# OIS_Anakart.net
KiCad netlist of a schematic drawn in Altium Designer
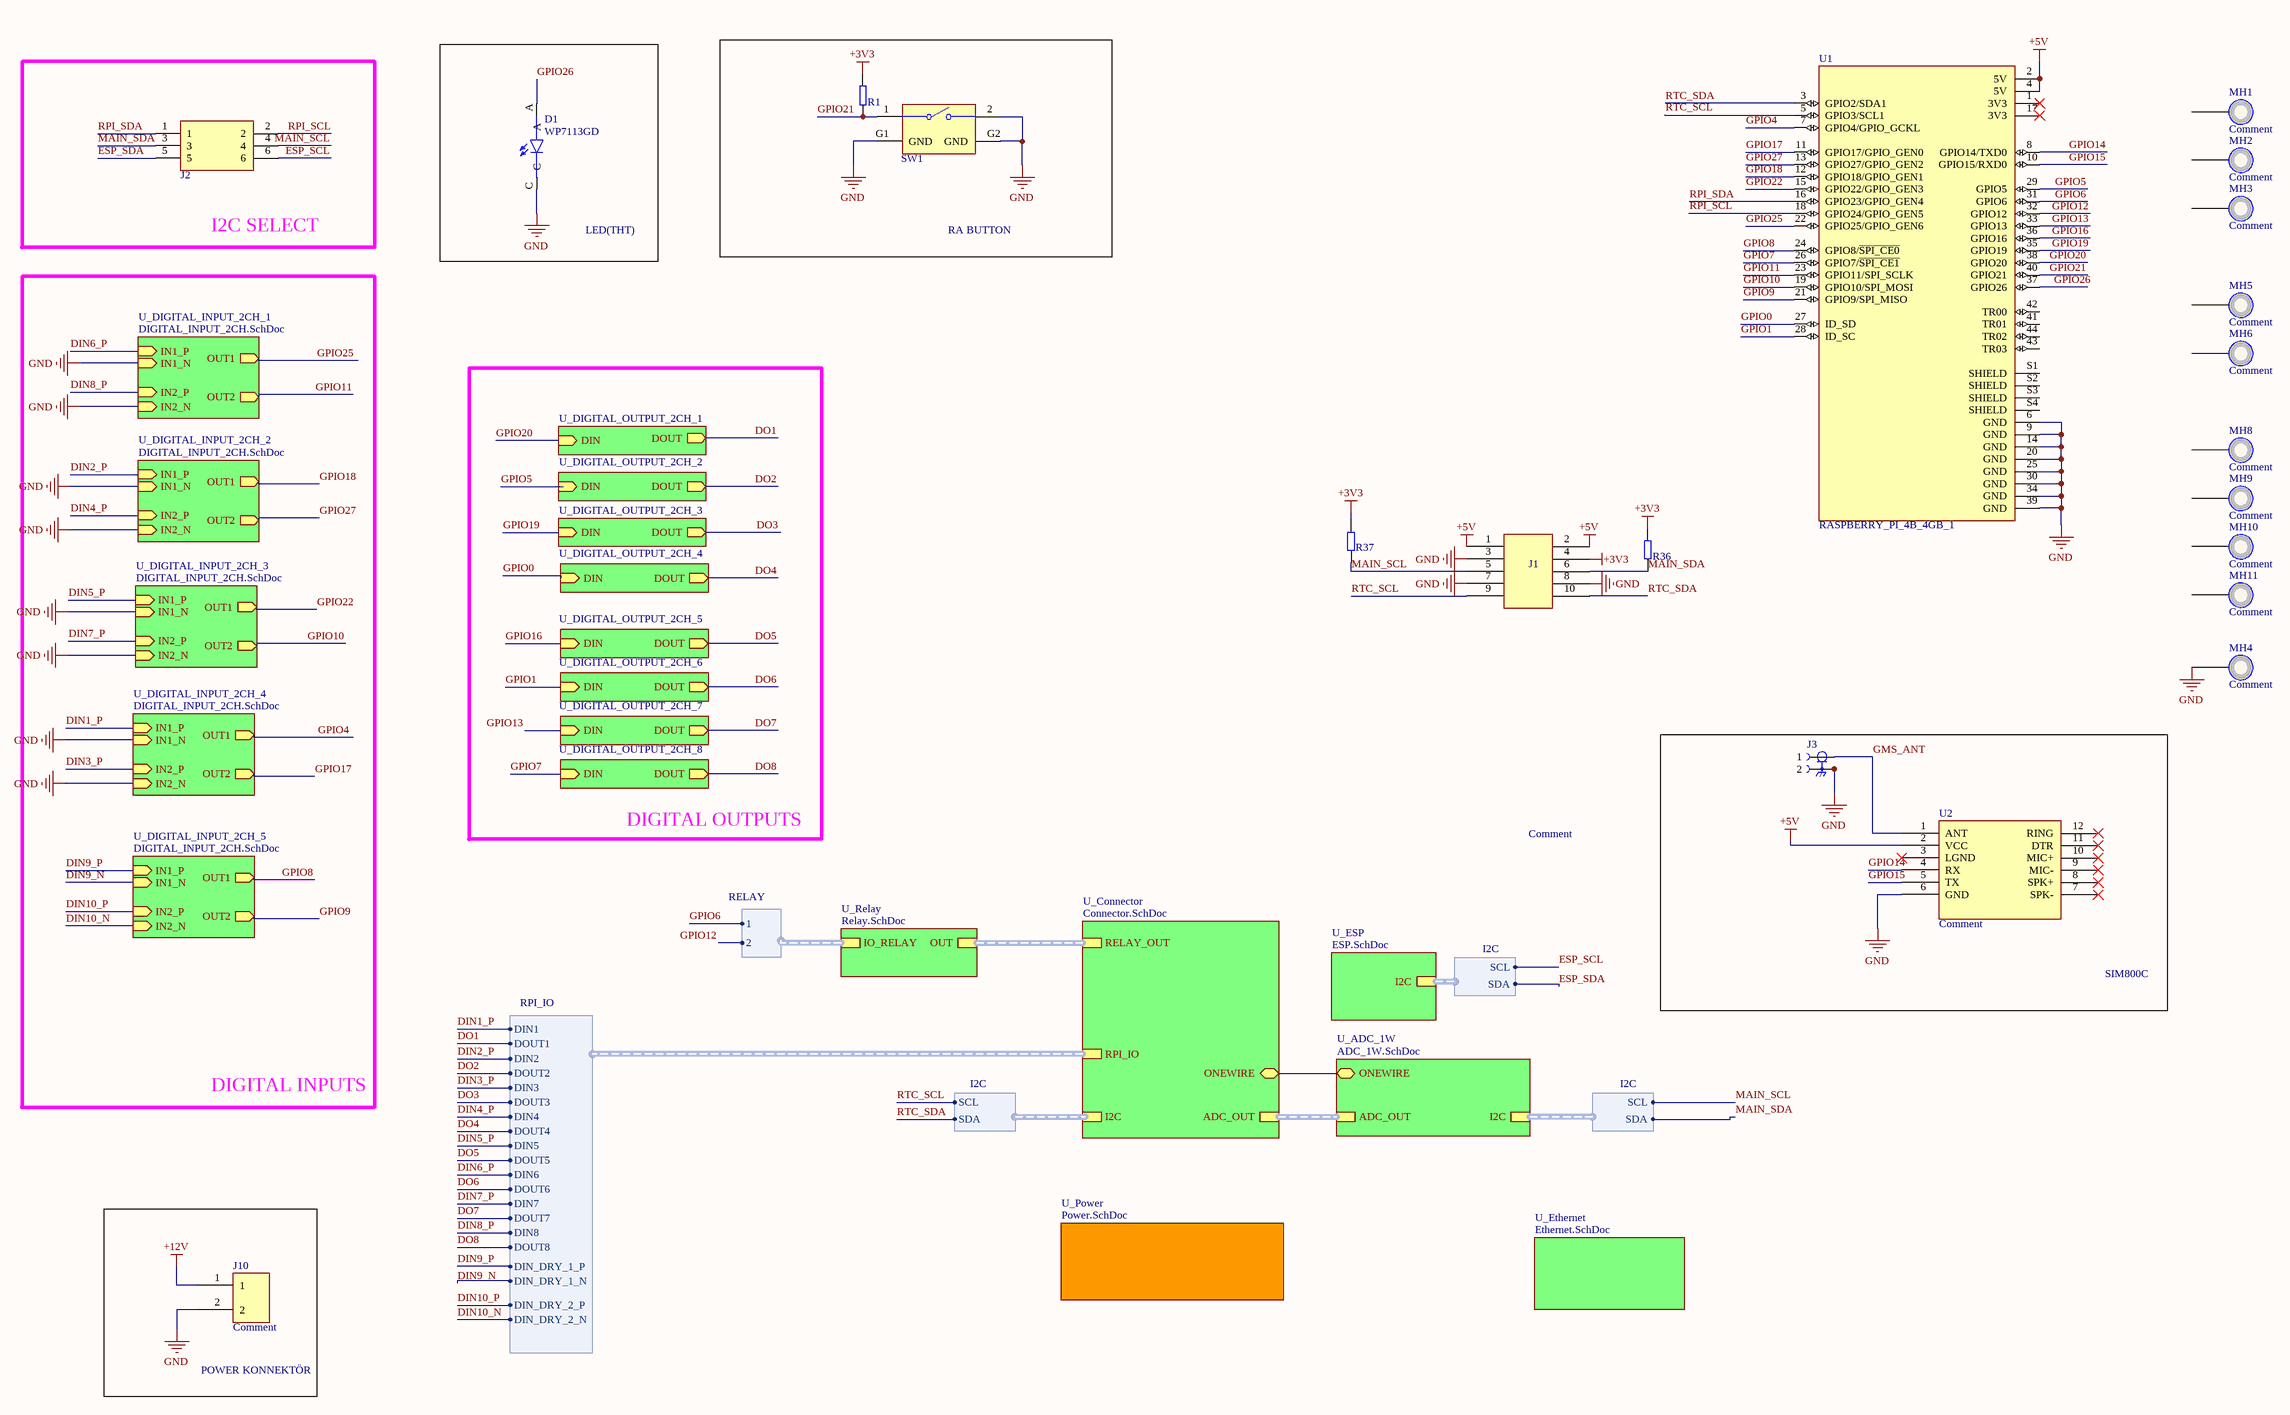
[diagram p0: OIS_Anakart.SchDoc]

(export (version "E")
  (design (tool "Eeschema 10.0.6"))
  (components
    (comp (ref "D1")
      (value "WP7113GD")
      (footprint "LED_WP7113GD")
      (description "Green 568nm LED Indication THT")
      (fields (field (name "MF") "Kingbright"))
      (libsource (lib "anayurt") (part "WP7113GD"))
    )
    (comp (ref "J1")
      (value "Comment")
      (footprint "2.54_5x2P")
      (description "CONN10P_5x2P")
      (libsource (lib "anayurt") (part "CONN10P_5x2P"))
    )
    (comp (ref "J2")
      (value "GRPB032VWQS-RC")
      (footprint "CONN_6P_1.27MM")
      (description "CONN HEADER SMD 6POS 1.27MM")
      (fields (field (name "MANUFACTURER") "Sullins Connector Solutions"))
      (libsource (lib "anayurt") (part "CONN_6P_2R"))
    )
    (comp (ref "J3")
      (value "RF2-49B-T-00-50-G-HDW")
      (footprint "ADAMTECH_RF2-49B-T-00-50-G-HDW")
      (description "RF SMA CONNECTOR")
      (fields (field (name "MF") "Adam Tech") (field (name "PART NUMBER") "2057-RF2-49B-T-00-50-G-HDW-ND"))
      (libsource (lib "anayurt") (part "RF2-49B-T-00-50-G-HDW"))
    )
    (comp (ref "J10")
      (value "Comment")
      (footprint "691213510002")
      (description "5.08 mm _ 2 pins")
      (fields (field (name "PART NUMBER") "2P_508"))
      (libsource (lib "anayurt") (part "CONN_2P"))
    )
    (comp (ref "MH1")
      (value "Comment")
      (footprint "m3_3.2x6")
      (fields (field (name "PART NUMBER") "M3_Vida") (field (name "CREATED BY") "Recep Aydin"))
      (libsource (lib "anayurt") (part "MountingHole"))
    )
    (comp (ref "MH2")
      (value "Comment")
      (footprint "m3_3.2x6")
      (fields (field (name "PART NUMBER") "M3_Vida") (field (name "CREATED BY") "Recep Aydin"))
      (libsource (lib "anayurt") (part "MountingHole"))
    )
    (comp (ref "MH3")
      (value "Comment")
      (footprint "m3_3.2x6")
      (fields (field (name "PART NUMBER") "M3_Vida") (field (name "CREATED BY") "Recep Aydin"))
      (libsource (lib "anayurt") (part "MountingHole"))
    )
    (comp (ref "MH4")
      (value "Comment")
      (footprint "m3_3.2x6")
      (fields (field (name "PART NUMBER") "M3_Vida") (field (name "CREATED BY") "Recep Aydin"))
      (libsource (lib "anayurt") (part "MountingHole"))
    )
    (comp (ref "MH5")
      (value "Comment")
      (footprint "m3_3.2x6")
      (fields (field (name "PART NUMBER") "M3_Vida") (field (name "CREATED BY") "Recep Aydin"))
      (libsource (lib "anayurt") (part "MountingHole"))
    )
    (comp (ref "MH6")
      (value "Comment")
      (footprint "m3_3.2x6")
      (fields (field (name "PART NUMBER") "M3_Vida") (field (name "CREATED BY") "Recep Aydin"))
      (libsource (lib "anayurt") (part "MountingHole"))
    )
    (comp (ref "MH8")
      (value "Comment")
      (footprint "m3_3.2x6")
      (fields (field (name "PART NUMBER") "M3_Vida") (field (name "CREATED BY") "Recep Aydin"))
      (libsource (lib "anayurt") (part "MountingHole"))
    )
    (comp (ref "MH9")
      (value "Comment")
      (footprint "m3_3.2x6")
      (fields (field (name "PART NUMBER") "M3_Vida") (field (name "CREATED BY") "Recep Aydin"))
      (libsource (lib "anayurt") (part "MountingHole"))
    )
    (comp (ref "MH10")
      (value "Comment")
      (footprint "m3_3.2x6")
      (fields (field (name "PART NUMBER") "M3_Vida") (field (name "CREATED BY") "Recep Aydin"))
      (libsource (lib "anayurt") (part "MountingHole"))
    )
    (comp (ref "MH11")
      (value "Comment")
      (footprint "m3_3.2x6")
      (fields (field (name "PART NUMBER") "M3_Vida") (field (name "CREATED BY") "Recep Aydin"))
      (libsource (lib "anayurt") (part "MountingHole"))
    )
    (comp (ref "R1")
      (value "1K")
      (footprint "R0402")
      (description "RES SMD 1K OHM 0.1% 1/16W 0402")
      (fields (field (name "PART NUMBER") "RT0402BRE071KL") (field (name "TOLERANCE") "0.1%"))
      (libsource (lib "anayurt") (part "RES"))
    )
    (comp (ref "R36")
      (value "1K")
      (footprint "R0402")
      (description "RES SMD 1K OHM 0.1% 1/16W 0402")
      (fields (field (name "PART NUMBER") "RT0402BRE071KL") (field (name "TOLERANCE") "0.1%"))
      (libsource (lib "anayurt") (part "RES"))
    )
    (comp (ref "R37")
      (value "1K")
      (footprint "R0402")
      (description "RES SMD 1K OHM 0.1% 1/16W 0402")
      (fields (field (name "PART NUMBER") "RT0402BRE071KL") (field (name "TOLERANCE") "0.1%"))
      (libsource (lib "anayurt") (part "RES"))
    )
    (comp (ref "SW1")
      (value "431256083716")
      (footprint "4312560837x6")
      (description "THT Tact Switch 6x6 mm Right Angled")
      (fields (field (name "MANUFACTURER") "Wurth Elektronik"))
      (libsource (lib "anayurt") (part "431256083716"))
    )
    (comp (ref "U1")
      (value "RASPBERRY_PI_4B_4GB_1")
      (footprint "MODULE_RASPBERRY_PI_4B_4GB_2")
      (description "MODULE_RASPBERRY_PI_4B_4GB")
      (fields (field (name "MF") "Raspberry Pi") (field (name "MP") "RASPBERRY PI 4B/4GB"))
      (libsource (lib "anayurt") (part "RASPBERRY_PI_4B_4GB_1"))
    )
    (comp (ref "U2")
      (value "Comment")
      (footprint "SIM800C_EVAL")
      (fields (field (name "PART NUMBER") "SIM800C_EVAL"))
      (libsource (lib "anayurt") (part "SIM800C_EVAL"))
    )
  )
  (nets
    (net (code "4") (name "+3V3") (class "Default")
      (node (ref "J1") (pin "4") (pinfunction "4_4") (pintype "passive"))
      (node (ref "R1") (pin "1") (pinfunction "1_1") (pintype "passive"))
      (node (ref "R36") (pin "1") (pinfunction "1_1") (pintype "passive"))
      (node (ref "R37") (pin "1") (pinfunction "1_1") (pintype "passive"))
    )
    (net (code "5") (name "+5V") (class "Default")
      (node (ref "J1") (pin "1") (pinfunction "1_1") (pintype "passive"))
      (node (ref "J1") (pin "2") (pinfunction "2_2") (pintype "passive"))
      (node (ref "U1") (pin "2") (pinfunction "5V_2") (pintype "power_in"))
      (node (ref "U1") (pin "4") (pinfunction "5V_4") (pintype "power_in"))
      (node (ref "U2") (pin "2") (pinfunction "VCC_2") (pintype "passive"))
    )
    (net (code "6") (name "+12V") (class "Default")
      (node (ref "J10") (pin "1") (pinfunction "1_1") (pintype "passive"))
    )
    (net (code "31") (name "/ESP_SCL") (class "Default")
      (node (ref "J2") (pin "6") (pinfunction "6_6") (pintype "passive"))
    )
    (net (code "32") (name "/ESP_SDA") (class "Default")
      (node (ref "J2") (pin "5") (pinfunction "5_5") (pintype "passive"))
    )
    (net (code "33") (name "/GMS_ANT") (class "Default")
      (node (ref "J3") (pin "1") (pinfunction "1_1") (pintype "passive"))
      (node (ref "U2") (pin "1") (pinfunction "ANT_1") (pintype "passive"))
    )
    (net (code "34") (name "/GPIO0") (class "Default")
      (node (ref "U1") (pin "27") (pinfunction "ID_SD_27") (pintype "bidirectional"))
    )
    (net (code "35") (name "/GPIO1") (class "Default")
      (node (ref "U1") (pin "28") (pinfunction "ID_SC_28") (pintype "bidirectional"))
    )
    (net (code "36") (name "/GPIO4") (class "Default")
      (node (ref "U1") (pin "7") (pinfunction "GPIO4/GPIO_GCKL_7") (pintype "bidirectional"))
    )
    (net (code "37") (name "/GPIO5") (class "Default")
      (node (ref "U1") (pin "29") (pinfunction "GPIO5_29") (pintype "bidirectional"))
    )
    (net (code "38") (name "/GPIO6") (class "Default")
      (node (ref "U1") (pin "31") (pinfunction "GPIO6_31") (pintype "bidirectional"))
    )
    (net (code "39") (name "/GPIO7") (class "Default")
      (node (ref "U1") (pin "26") (pinfunction "GPIO7/~{SPI_CE1}_26") (pintype "bidirectional"))
    )
    (net (code "40") (name "/GPIO8") (class "Default")
      (node (ref "U1") (pin "24") (pinfunction "GPIO8/~{SPI_CE0}_24") (pintype "bidirectional"))
    )
    (net (code "41") (name "/GPIO9") (class "Default")
      (node (ref "U1") (pin "21") (pinfunction "GPIO9/SPI_MISO_21") (pintype "bidirectional"))
    )
    (net (code "42") (name "/GPIO10") (class "Default")
      (node (ref "U1") (pin "19") (pinfunction "GPIO10/SPI_MOSI_19") (pintype "bidirectional"))
    )
    (net (code "43") (name "/GPIO11") (class "Default")
      (node (ref "U1") (pin "23") (pinfunction "GPIO11/SPI_SCLK_23") (pintype "bidirectional"))
    )
    (net (code "44") (name "/GPIO12") (class "Default")
      (node (ref "U1") (pin "32") (pinfunction "GPIO12_32") (pintype "bidirectional"))
    )
    (net (code "45") (name "/GPIO13") (class "Default")
      (node (ref "U1") (pin "33") (pinfunction "GPIO13_33") (pintype "bidirectional"))
    )
    (net (code "46") (name "/GPIO14") (class "Default")
      (node (ref "U1") (pin "8") (pinfunction "GPIO14/TXD0_8") (pintype "bidirectional"))
      (node (ref "U2") (pin "4") (pinfunction "RX_4") (pintype "passive"))
    )
    (net (code "47") (name "/GPIO15") (class "Default")
      (node (ref "U1") (pin "10") (pinfunction "GPIO15/RXD0_10") (pintype "bidirectional"))
      (node (ref "U2") (pin "5") (pinfunction "TX_5") (pintype "passive"))
    )
    (net (code "48") (name "/GPIO16") (class "Default")
      (node (ref "U1") (pin "36") (pinfunction "GPIO16_36") (pintype "bidirectional"))
    )
    (net (code "49") (name "/GPIO17") (class "Default")
      (node (ref "U1") (pin "11") (pinfunction "GPIO17/GPIO_GEN0_11") (pintype "bidirectional"))
    )
    (net (code "50") (name "/GPIO18") (class "Default")
      (node (ref "U1") (pin "12") (pinfunction "GPIO18/GPIO_GEN1_12") (pintype "bidirectional"))
    )
    (net (code "51") (name "/GPIO19") (class "Default")
      (node (ref "U1") (pin "35") (pinfunction "GPIO19_35") (pintype "bidirectional"))
    )
    (net (code "52") (name "/GPIO20") (class "Default")
      (node (ref "U1") (pin "38") (pinfunction "GPIO20_38") (pintype "bidirectional"))
    )
    (net (code "53") (name "/GPIO21") (class "Default")
      (node (ref "R1") (pin "2") (pinfunction "2_2") (pintype "passive"))
      (node (ref "SW1") (pin "1") (pinfunction "1_1") (pintype "passive"))
      (node (ref "U1") (pin "40") (pinfunction "GPIO21_40") (pintype "bidirectional"))
    )
    (net (code "54") (name "/GPIO22") (class "Default")
      (node (ref "U1") (pin "15") (pinfunction "GPIO22/GPIO_GEN3_15") (pintype "bidirectional"))
    )
    (net (code "55") (name "/GPIO25") (class "Default")
      (node (ref "U1") (pin "22") (pinfunction "GPIO25/GPIO_GEN6_22") (pintype "bidirectional"))
    )
    (net (code "56") (name "/GPIO26") (class "Default")
      (node (ref "D1") (pin "A") (pinfunction "A_A") (pintype "passive"))
      (node (ref "U1") (pin "37") (pinfunction "GPIO26_37") (pintype "bidirectional"))
    )
    (net (code "57") (name "/GPIO27") (class "Default")
      (node (ref "U1") (pin "13") (pinfunction "GPIO27/GPIO_GEN2_13") (pintype "bidirectional"))
    )
    (net (code "67") (name "/MAIN_SCL") (class "Default")
      (node (ref "J1") (pin "5") (pinfunction "5_5") (pintype "passive"))
      (node (ref "J2") (pin "4") (pinfunction "4_4") (pintype "passive"))
      (node (ref "R37") (pin "2") (pinfunction "2_2") (pintype "passive"))
    )
    (net (code "68") (name "/MAIN_SDA") (class "Default")
      (node (ref "J1") (pin "6") (pinfunction "6_6") (pintype "passive"))
      (node (ref "J2") (pin "3") (pinfunction "3_3") (pintype "passive"))
      (node (ref "R36") (pin "2") (pinfunction "2_2") (pintype "passive"))
    )
    (net (code "73") (name "/RPI_SCL") (class "Default")
      (node (ref "J2") (pin "2") (pinfunction "2_2") (pintype "passive"))
      (node (ref "U1") (pin "18") (pinfunction "GPIO24/GPIO_GEN5_18") (pintype "bidirectional"))
    )
    (net (code "74") (name "/RPI_SDA") (class "Default")
      (node (ref "J2") (pin "1") (pinfunction "1_1") (pintype "passive"))
      (node (ref "U1") (pin "16") (pinfunction "GPIO23/GPIO_GEN4_16") (pintype "bidirectional"))
    )
    (net (code "75") (name "/RTC_SCL") (class "Default")
      (node (ref "J1") (pin "9") (pinfunction "9_9") (pintype "passive"))
      (node (ref "U1") (pin "5") (pinfunction "GPIO3/SCL1_5") (pintype "bidirectional"))
    )
    (net (code "76") (name "/RTC_SDA") (class "Default")
      (node (ref "J1") (pin "10") (pinfunction "10_10") (pintype "passive"))
      (node (ref "U1") (pin "3") (pinfunction "GPIO2/SDA1_3") (pintype "bidirectional"))
    )
    (net (code "80") (name "GND") (class "Default")
      (node (ref "D1") (pin "C") (pinfunction "C_C") (pintype "passive"))
      (node (ref "J1") (pin "3") (pinfunction "3_3") (pintype "passive"))
      (node (ref "J1") (pin "7") (pinfunction "7_7") (pintype "passive"))
      (node (ref "J1") (pin "8") (pinfunction "8_8") (pintype "passive"))
      (node (ref "J10") (pin "2") (pinfunction "2_2") (pintype "passive"))
      (node (ref "J3") (pin "SH1") (pinfunction "2_SH1") (pintype "passive"))
      (node (ref "J3") (pin "SH2") (pinfunction "2_SH2") (pintype "passive"))
      (node (ref "J3") (pin "SH3") (pinfunction "2_SH3") (pintype "passive"))
      (node (ref "J3") (pin "SH4") (pinfunction "2_SH4") (pintype "passive"))
      (node (ref "MH4") (pin "1") (pinfunction "1_1") (pintype "passive"))
      (node (ref "SW1") (pin "2") (pinfunction "2_2") (pintype "passive"))
      (node (ref "SW1") (pin "G1") (pinfunction "GND_G1") (pintype "passive"))
      (node (ref "SW1") (pin "G2") (pinfunction "GND_G2") (pintype "passive"))
      (node (ref "U1") (pin "14") (pinfunction "GND_14") (pintype "power_in"))
      (node (ref "U1") (pin "20") (pinfunction "GND_20") (pintype "power_in"))
      (node (ref "U1") (pin "25") (pinfunction "GND_25") (pintype "power_in"))
      (node (ref "U1") (pin "30") (pinfunction "GND_30") (pintype "power_in"))
      (node (ref "U1") (pin "34") (pinfunction "GND_34") (pintype "power_in"))
      (node (ref "U1") (pin "39") (pinfunction "GND_39") (pintype "power_in"))
      (node (ref "U1") (pin "6") (pinfunction "GND_6") (pintype "power_in"))
      (node (ref "U1") (pin "9") (pinfunction "GND_9") (pintype "power_in"))
      (node (ref "U2") (pin "6") (pinfunction "GND_6") (pintype "passive"))
    )
    (net (code "81") (name "unconnected-(MH1-Pad1)") (class "Default")
      (node (ref "MH1") (pin "1") (pinfunction "1_1") (pintype "passive"))
    )
    (net (code "82") (name "unconnected-(MH2-Pad1)") (class "Default")
      (node (ref "MH2") (pin "1") (pinfunction "1_1") (pintype "passive"))
    )
    (net (code "83") (name "unconnected-(MH3-Pad1)") (class "Default")
      (node (ref "MH3") (pin "1") (pinfunction "1_1") (pintype "passive"))
    )
    (net (code "84") (name "unconnected-(MH5-Pad1)") (class "Default")
      (node (ref "MH5") (pin "1") (pinfunction "1_1") (pintype "passive"))
    )
    (net (code "85") (name "unconnected-(MH6-Pad1)") (class "Default")
      (node (ref "MH6") (pin "1") (pinfunction "1_1") (pintype "passive"))
    )
    (net (code "86") (name "unconnected-(MH8-Pad1)") (class "Default")
      (node (ref "MH8") (pin "1") (pinfunction "1_1") (pintype "passive"))
    )
    (net (code "87") (name "unconnected-(MH9-Pad1)") (class "Default")
      (node (ref "MH9") (pin "1") (pinfunction "1_1") (pintype "passive"))
    )
    (net (code "88") (name "unconnected-(MH10-Pad1)") (class "Default")
      (node (ref "MH10") (pin "1") (pinfunction "1_1") (pintype "passive"))
    )
    (net (code "89") (name "unconnected-(MH11-Pad1)") (class "Default")
      (node (ref "MH11") (pin "1") (pinfunction "1_1") (pintype "passive"))
    )
    (net (code "90") (name "unconnected-(U1-3V3-Pad1)") (class "Default")
      (node (ref "U1") (pin "1") (pinfunction "3V3_1") (pintype "power_in+no_connect"))
    )
    (net (code "91") (name "unconnected-(U1-3V3-Pad17)") (class "Default")
      (node (ref "U1") (pin "17") (pinfunction "3V3_17") (pintype "power_in+no_connect"))
    )
    (net (code "92") (name "unconnected-(U1-SHIELD-PadS1)") (class "Default")
      (node (ref "U1") (pin "S1") (pinfunction "SHIELD_S1") (pintype "power_in"))
    )
    (net (code "93") (name "unconnected-(U1-SHIELD-PadS2)") (class "Default")
      (node (ref "U1") (pin "S2") (pinfunction "SHIELD_S2") (pintype "power_in"))
    )
    (net (code "94") (name "unconnected-(U1-SHIELD-PadS3)") (class "Default")
      (node (ref "U1") (pin "S3") (pinfunction "SHIELD_S3") (pintype "power_in"))
    )
    (net (code "95") (name "unconnected-(U1-SHIELD-PadS4)") (class "Default")
      (node (ref "U1") (pin "S4") (pinfunction "SHIELD_S4") (pintype "power_in"))
    )
    (net (code "96") (name "unconnected-(U1-TR00-Pad42)") (class "Default")
      (node (ref "U1") (pin "42") (pinfunction "TR00_42") (pintype "bidirectional"))
    )
    (net (code "97") (name "unconnected-(U1-TR01-Pad41)") (class "Default")
      (node (ref "U1") (pin "41") (pinfunction "TR01_41") (pintype "bidirectional"))
    )
    (net (code "98") (name "unconnected-(U1-TR02-Pad44)") (class "Default")
      (node (ref "U1") (pin "44") (pinfunction "TR02_44") (pintype "bidirectional"))
    )
    (net (code "99") (name "unconnected-(U1-TR03-Pad43)") (class "Default")
      (node (ref "U1") (pin "43") (pinfunction "TR03_43") (pintype "bidirectional"))
    )
    (net (code "100") (name "unconnected-(U2-DTR-Pad11)") (class "Default")
      (node (ref "U2") (pin "11") (pinfunction "DTR_11") (pintype "passive+no_connect"))
    )
    (net (code "101") (name "unconnected-(U2-LGND-Pad3)") (class "Default")
      (node (ref "U2") (pin "3") (pinfunction "LGND_3") (pintype "passive+no_connect"))
    )
    (net (code "102") (name "unconnected-(U2-MIC+-Pad10)") (class "Default")
      (node (ref "U2") (pin "10") (pinfunction "MIC+_10") (pintype "passive+no_connect"))
    )
    (net (code "103") (name "unconnected-(U2-MIC--Pad9)") (class "Default")
      (node (ref "U2") (pin "9") (pinfunction "MIC-_9") (pintype "passive+no_connect"))
    )
    (net (code "104") (name "unconnected-(U2-RING-Pad12)") (class "Default")
      (node (ref "U2") (pin "12") (pinfunction "RING_12") (pintype "passive+no_connect"))
    )
    (net (code "105") (name "unconnected-(U2-SPK+-Pad8)") (class "Default")
      (node (ref "U2") (pin "8") (pinfunction "SPK+_8") (pintype "passive+no_connect"))
    )
    (net (code "106") (name "unconnected-(U2-SPK--Pad7)") (class "Default")
      (node (ref "U2") (pin "7") (pinfunction "SPK-_7") (pintype "passive+no_connect"))
    )
  )
)
